# IoT_Greenhouse_V1_0_A_-_Esp32.net
KiCad netlist of a schematic drawn in Altium Designer
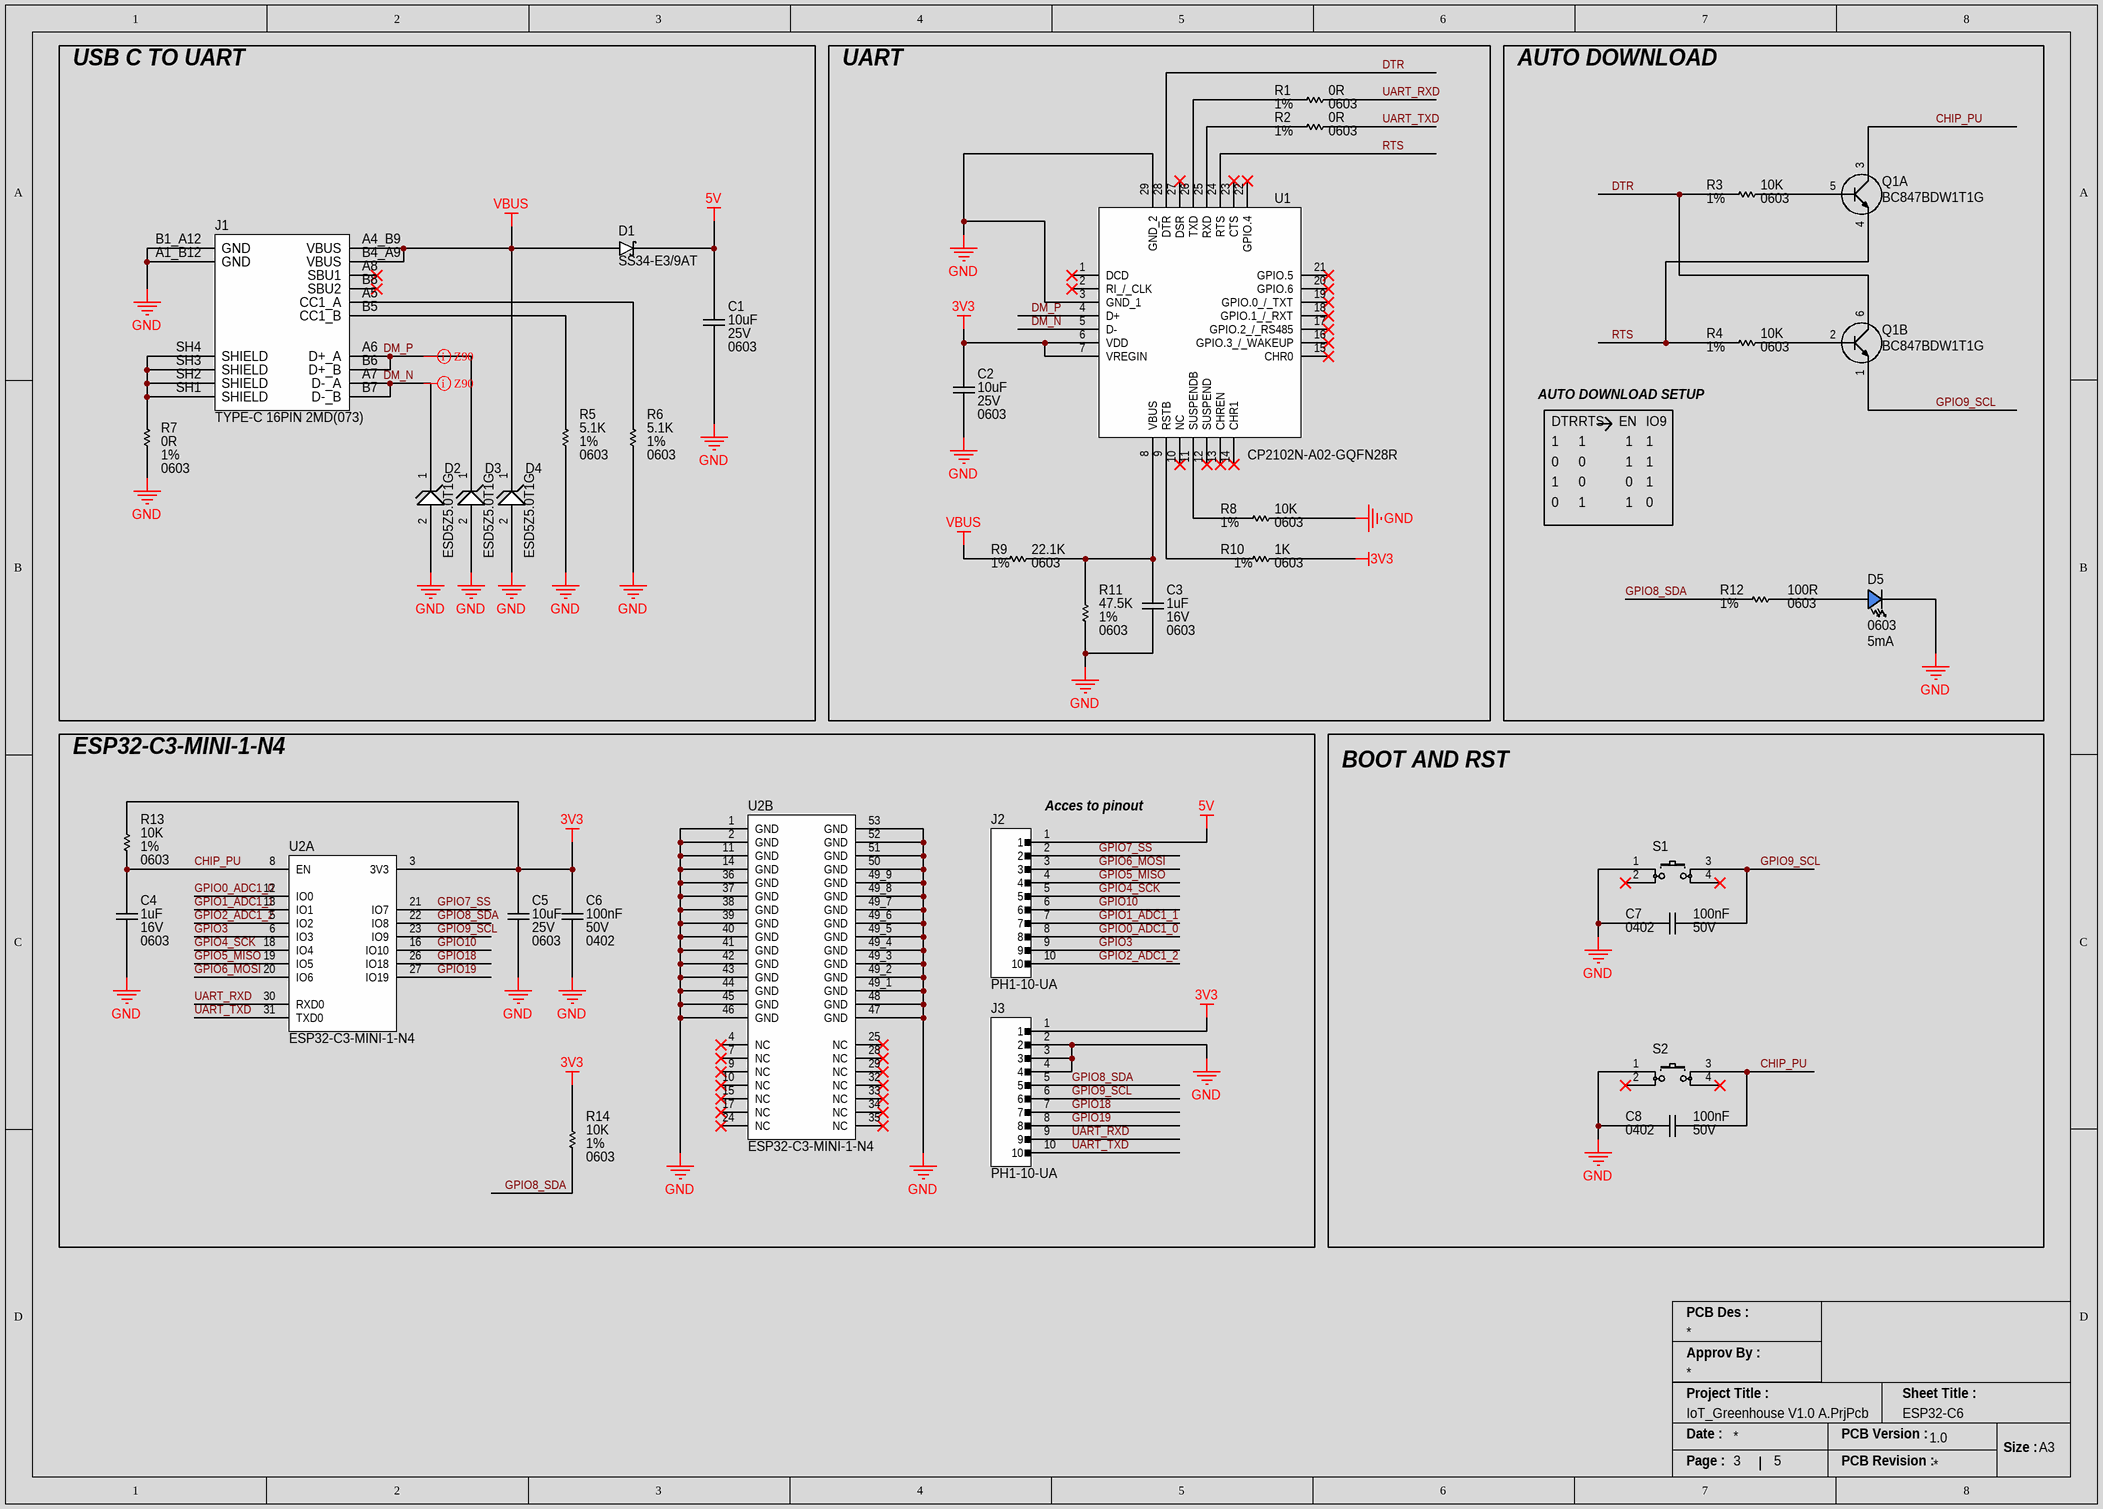
[diagram p0: IoT_Greenhouse V1.0 A - Esp32.SchDoc]

(export (version "E")
  (design (tool "Eeschema 10.0.6"))
  (components
    (comp (ref "C1")
      (value "GRM188R61E106MA73D")
      (footprint "CAP_0603_CAPC1608X08N")
      (description "Multilayer Ceramic Capacitor, 10 uF, 25 V, ± 20%, X5R, 0603 [1608 Metric]")
      (fields
        (field (name "MANUFACTURER") "Murata")
        (field (name "TOLERANCE") "20%")
        (field (name "CASE/PACKAGE") "0603")
        (field (name "CAPACITANCE") "10uF")
        (field (name "VOLTAGE RATING") "25V")
      )
      (libsource (lib "Electronic Devices_LIB") (part "CAP_10UF_25V_X5R_0603"))
    )
    (comp (ref "C2")
      (value "GRM188R61E106MA73D")
      (footprint "CAP_0603_CAPC1608X08N")
      (description "Multilayer Ceramic Capacitor, 10 uF, 25 V, ± 20%, X5R, 0603 [1608 Metric]")
      (fields
        (field (name "MANUFACTURER") "Murata")
        (field (name "TOLERANCE") "20%")
        (field (name "CASE/PACKAGE") "0603")
        (field (name "CAPACITANCE") "10uF")
        (field (name "VOLTAGE RATING") "25V")
      )
      (libsource (lib "Electronic Devices_LIB") (part "CAP_10UF_25V_X5R_0603"))
    )
    (comp (ref "C3")
      (value "CL10A105KO8NNNC")
      (footprint "CAP_0603_CAPC1608X08N")
      (description "CAP CER 1UF 16V X5R 0603")
      (fields
        (field (name "MANUFACTURER") "Samsung")
        (field (name "TOLERANCE") "10%")
        (field (name "VOLTAGE RATING") "16V")
        (field (name "CAPACITANCE") "1uF")
        (field (name "CASE/PACKAGE") "0603")
      )
      (libsource (lib "Electronic Devices_LIB") (part "CAP_1UF_16V_X5R_0603"))
    )
    (comp (ref "C4")
      (value "CL10A105KO8NNNC")
      (footprint "CAP_0603_CAPC1608X08N")
      (description "CAP CER 1UF 16V X5R 0603")
      (fields
        (field (name "MANUFACTURER") "Samsung")
        (field (name "TOLERANCE") "10%")
        (field (name "VOLTAGE RATING") "16V")
        (field (name "CAPACITANCE") "1uF")
        (field (name "CASE/PACKAGE") "0603")
      )
      (libsource (lib "Electronic Devices_LIB") (part "CAP_1UF_16V_X5R_0603"))
    )
    (comp (ref "C5")
      (value "GRM188R61E106MA73D")
      (footprint "CAP_0603_CAPC1608X08N")
      (description "Multilayer Ceramic Capacitor, 10 uF, 25 V, ± 20%, X5R, 0603 [1608 Metric]")
      (fields
        (field (name "MANUFACTURER") "Murata")
        (field (name "TOLERANCE") "20%")
        (field (name "CASE/PACKAGE") "0603")
        (field (name "CAPACITANCE") "10uF")
        (field (name "VOLTAGE RATING") "25V")
      )
      (libsource (lib "Electronic Devices_LIB") (part "CAP_10UF_25V_X5R_0603"))
    )
    (comp (ref "C6")
      (value "GRM155R71H104KE14D")
      (footprint "CAP_0402_CAPC1005X05N")
      (description "Multilayer Ceramic Capacitor, 0.1 uF, 16 V, ± 10%, X7R, 0402 [1005 Metric]")
      (fields
        (field (name "MANUFACTURER") "Murata")
        (field (name "TOLERANCE") "10%")
        (field (name "VOLTAGE RATING") "50V")
        (field (name "CAPACITANCE") "100nF")
        (field (name "CASE/PACKAGE") "0402")
      )
      (libsource (lib "Electronic Devices_LIB") (part "CAP_100NF_50V_X7R_0402"))
    )
    (comp (ref "C7")
      (value "GRM155R71H104KE14D")
      (footprint "CAP_0402_CAPC1005X05N")
      (description "Multilayer Ceramic Capacitor, 0.1 uF, 16 V, ± 10%, X7R, 0402 [1005 Metric]")
      (fields
        (field (name "MANUFACTURER") "Murata")
        (field (name "TOLERANCE") "10%")
        (field (name "VOLTAGE RATING") "50V")
        (field (name "CAPACITANCE") "100nF")
        (field (name "CASE/PACKAGE") "0402")
      )
      (libsource (lib "Electronic Devices_LIB") (part "CAP_100NF_50V_X7R_0402"))
    )
    (comp (ref "C8")
      (value "GRM155R71H104KE14D")
      (footprint "CAP_0402_CAPC1005X05N")
      (description "Multilayer Ceramic Capacitor, 0.1 uF, 16 V, ± 10%, X7R, 0402 [1005 Metric]")
      (fields
        (field (name "MANUFACTURER") "Murata")
        (field (name "TOLERANCE") "10%")
        (field (name "VOLTAGE RATING") "50V")
        (field (name "CAPACITANCE") "100nF")
        (field (name "CASE/PACKAGE") "0402")
      )
      (libsource (lib "Electronic Devices_LIB") (part "CAP_100NF_50V_X7R_0402"))
    )
    (comp (ref "D1")
      (value "SS34-E3/9AT")
      (footprint "DIO_Vishay_SMC_MFG")
      (description "Rectifier Diode, schottky, 40V V(Rrm), do-214Ab / Smc")
      (fields (field (name "MANUFACTURER") "Vishay Semiconductors"))
      (libsource (lib "Electronic Devices_LIB") (part "DIO_SCTKY_40V_3A"))
    )
    (comp (ref "D2")
      (value "ESD5Z5.0T1G")
      (footprint "SOD523_SODFL1608X70N")
      (description "ESD5Z Series 6.2 V 80 pF 5 Vrwm TVS and ESD Protection Diodes - SOD-523")
      (fields (field (name "MANUFACTURER") "ON Semiconductor"))
      (libsource (lib "Electronic Devices_LIB") (part "DIO_TVS_5V_ESD5Z5.0T1G"))
    )
    (comp (ref "D3")
      (value "ESD5Z5.0T1G")
      (footprint "SOD523_SODFL1608X70N")
      (description "ESD5Z Series 6.2 V 80 pF 5 Vrwm TVS and ESD Protection Diodes - SOD-523")
      (fields (field (name "MANUFACTURER") "ON Semiconductor"))
      (libsource (lib "Electronic Devices_LIB") (part "DIO_TVS_5V_ESD5Z5.0T1G"))
    )
    (comp (ref "D4")
      (value "ESD5Z5.0T1G")
      (footprint "SOD523_SODFL1608X70N")
      (description "ESD5Z Series 6.2 V 80 pF 5 Vrwm TVS and ESD Protection Diodes - SOD-523")
      (fields (field (name "MANUFACTURER") "ON Semiconductor"))
      (libsource (lib "Electronic Devices_LIB") (part "DIO_TVS_5V_ESD5Z5.0T1G"))
    )
    (comp (ref "D5")
      (value "LTST-C193TBKT-5A")
      (footprint "LED_0603-BLUE-0.75mm")
      (description "LED Uni-Color Blue 468nm 2-Pin Chip LED T/R")
      (fields
        (field (name "MANUFACTURER") "Vishay Lite-On")
        (field (name "CASE CODE (IMPERIAL)") "0603")
        (field (name "TEST CURRENT") "5mA")
      )
      (libsource (lib "Electronic Devices_LIB") (part "LED_DIO_BLUE_5mA_0603"))
    )
    (comp (ref "J1")
      (value "TYPE-C 16PIN 2MD(073)")
      (footprint "CONN_USB_C_16P")
      (description "5A 1 Surface Mount 16P Female -25℃~+85℃ Type-C SMD USB Connectors ROHS")
      (fields (field (name "MANUFACTURER") "SHOU HAN"))
      (libsource (lib "Electronic Devices_LIB") (part "CONN_USB_TYPEC_2.0_16P_TYPE-C 16PIN 2MD(073)"))
    )
    (comp (ref "J2")
      (value "PH1-10-UA")
      (footprint "CONN_HEADER_MALE_10P")
      (description "Conn Unshrouded Header HDR 12 POS 2.54mm Solder RA Side Entry Thru-Hole Bag")
      (fields (field (name "MANUFACTURER") "Adam Equipment"))
      (libsource (lib "Electronic Devices_LIB") (part "CONN_HEADER_MALE_10P_2.54mm_PH1-10-UA"))
    )
    (comp (ref "J3")
      (value "PH1-10-UA")
      (footprint "CONN_HEADER_MALE_10P")
      (description "Conn Unshrouded Header HDR 12 POS 2.54mm Solder RA Side Entry Thru-Hole Bag")
      (fields (field (name "MANUFACTURER") "Adam Equipment"))
      (libsource (lib "Electronic Devices_LIB") (part "CONN_HEADER_MALE_10P_2.54mm_PH1-10-UA"))
    )
    (comp (ref "Q1")
      (value "BC847BDW1T1G")
      (footprint "TRANS_BJT_SOT65P210X110-6N")
      (description "ON Semi BC847BDW1T1G Dual NPN Bipolar Transistor; 0.1 A; 45 V; 6-Pin SC-88")
      (fields (field (name "MANUFACTURER") "ON Semiconductor"))
      (libsource (lib "Electronic Devices_LIB") (part "TRANS_BIPOLAR_NPN_BC847BDW1T1G"))
    )
    (comp (ref "R1")
      (value "RC0603FR-070RL")
      (footprint "RES_0603_RESC1608X04N")
      (description "RC Series 0603 0.1 W 0 Ohm Jumper Surface Mount Thick Film Chip Resistor")
      (fields
        (field (name "MANUFACTURER") "Yageo")
        (field (name "TOLERANCE") "1%")
        (field (name "RESISTANCE") "0R")
        (field (name "CASE CODE (IMPERIAL)") "0603")
      )
      (libsource (lib "Electronic Devices_LIB") (part "RES_0R_1%_100mW_0603"))
    )
    (comp (ref "R2")
      (value "RC0603FR-070RL")
      (footprint "RES_0603_RESC1608X04N")
      (description "RC Series 0603 0.1 W 0 Ohm Jumper Surface Mount Thick Film Chip Resistor")
      (fields
        (field (name "MANUFACTURER") "Yageo")
        (field (name "TOLERANCE") "1%")
        (field (name "RESISTANCE") "0R")
        (field (name "CASE CODE (IMPERIAL)") "0603")
      )
      (libsource (lib "Electronic Devices_LIB") (part "RES_0R_1%_100mW_0603"))
    )
    (comp (ref "R3")
      (value "AC0603FR-1010KL")
      (footprint "RES_0603_RESC1608X04N")
      (description "Chip Resistor Automotive Grade Thick Film 0603 10kOhm 1% Paper T/R")
      (fields
        (field (name "MANUFACTURER") "Yageo")
        (field (name "RESISTANCE") "10K")
        (field (name "TOLERANCE") "1%")
        (field (name "CASE/PACKAGE") "0603")
      )
      (libsource (lib "Electronic Devices_LIB") (part "RES_10K_1%_100mW_0603"))
    )
    (comp (ref "R4")
      (value "AC0603FR-1010KL")
      (footprint "RES_0603_RESC1608X04N")
      (description "Chip Resistor Automotive Grade Thick Film 0603 10kOhm 1% Paper T/R")
      (fields
        (field (name "MANUFACTURER") "Yageo")
        (field (name "RESISTANCE") "10K")
        (field (name "TOLERANCE") "1%")
        (field (name "CASE/PACKAGE") "0603")
      )
      (libsource (lib "Electronic Devices_LIB") (part "RES_10K_1%_100mW_0603"))
    )
    (comp (ref "R5")
      (value "RC0603FR-075K1L")
      (footprint "RES_0603_RESC1608X04N")
      (description "SMD Chip Resistor, 5.1 kOhm, ± 1%, 100 mW, 0603 [1608 Metric], Thick Film, General Purpose")
      (fields
        (field (name "MANUFACTURER") "Yageo")
        (field (name "TOLERANCE") "1%")
        (field (name "RESISTANCE") "5.1K")
        (field (name "CASE/PACKAGE") "0603")
      )
      (libsource (lib "Electronic Devices_LIB") (part "RES_5.1K_1%_100mW_0603"))
    )
    (comp (ref "R6")
      (value "RC0603FR-075K1L")
      (footprint "RES_0603_RESC1608X04N")
      (description "SMD Chip Resistor, 5.1 kOhm, ± 1%, 100 mW, 0603 [1608 Metric], Thick Film, General Purpose")
      (fields
        (field (name "MANUFACTURER") "Yageo")
        (field (name "TOLERANCE") "1%")
        (field (name "RESISTANCE") "5.1K")
        (field (name "CASE/PACKAGE") "0603")
      )
      (libsource (lib "Electronic Devices_LIB") (part "RES_5.1K_1%_100mW_0603"))
    )
    (comp (ref "R7")
      (value "RC0603FR-070RL")
      (footprint "RES_0603_RESC1608X04N")
      (description "RC Series 0603 0.1 W 0 Ohm Jumper Surface Mount Thick Film Chip Resistor")
      (fields
        (field (name "MANUFACTURER") "Yageo")
        (field (name "TOLERANCE") "1%")
        (field (name "RESISTANCE") "0R")
        (field (name "CASE CODE (IMPERIAL)") "0603")
      )
      (libsource (lib "Electronic Devices_LIB") (part "RES_0R_1%_100mW_0603"))
    )
    (comp (ref "R8")
      (value "AC0603FR-1010KL")
      (footprint "RES_0603_RESC1608X04N")
      (description "Chip Resistor Automotive Grade Thick Film 0603 10kOhm 1% Paper T/R")
      (fields
        (field (name "MANUFACTURER") "Yageo")
        (field (name "RESISTANCE") "10K")
        (field (name "TOLERANCE") "1%")
        (field (name "CASE/PACKAGE") "0603")
      )
      (libsource (lib "Electronic Devices_LIB") (part "RES_10K_1%_100mW_0603"))
    )
    (comp (ref "R9")
      (value "RC0603FR-0722K1L")
      (footprint "RES_0603_RESC1608X04N")
      (description "SMD Chip Resistor, 22.1 kOhm, ± 1%, 100 mW, 0603 [1608 Metric], Thick Film, General Purpose")
      (fields
        (field (name "MANUFACTURER") "Yageo")
        (field (name "RESISTANCE") "22.1K")
        (field (name "TOLERANCE") "1%")
        (field (name "CASE/PACKAGE") "0603")
      )
      (libsource (lib "Electronic Devices_LIB") (part "RES_22.1K_1%_100mW_0603"))
    )
    (comp (ref "R10")
      (value "AC0603FR-101KL")
      (footprint "RES_0603_RESC1608X04N")
      (description "Chip Resistor Automotive Grade Thick Film 0603 1kOhm 1% Paper T/R")
      (fields
        (field (name "MANUFACTURER") "Yageo")
        (field (name "RESISTANCE") "1K")
        (field (name "TOLERANCE") "1%")
        (field (name "CASE/PACKAGE") "0603")
      )
      (libsource (lib "Electronic Devices_LIB") (part "RES_1K_1%_100mW_0603"))
    )
    (comp (ref "R11")
      (value "AC0603FR-0747K5L")
      (footprint "RES_0603_RESC1608X04N")
      (description "SMD Chip Resistor, 47.5 kOhm, ± 1%, 100 mW, 0603 [1608 Metric], Thick Film, General Purpose")
      (fields
        (field (name "MANUFACTURER") "Yageo")
        (field (name "TOLERANCE") "1%")
        (field (name "RESISTANCE") "47.5K")
        (field (name "CASE/PACKAGE") "0603")
      )
      (libsource (lib "Electronic Devices_LIB") (part "RES_47.5K_1%_100mW_0603"))
    )
    (comp (ref "R12")
      (value "ERJ3EKF1000V")
      (footprint "CAP_0603_CAPC1608X08N")
      (description "Res Thick Film 0603 100 Ohm 1% 1/10W ±100ppm/°C Molded SMD Punched Carrier T/R")
      (fields
        (field (name "MANUFACTURER") "Panasonic")
        (field (name "CASE CODE (IMPERIAL)") "0603")
        (field (name "TOLERANCE") "1%")
        (field (name "RESISTANCE") "100R")
      )
      (libsource (lib "Electronic Devices_LIB") (part "RES_100R_1%_100MW_0603"))
    )
    (comp (ref "R13")
      (value "AC0603FR-1010KL")
      (footprint "RES_0603_RESC1608X04N")
      (description "Chip Resistor Automotive Grade Thick Film 0603 10kOhm 1% Paper T/R")
      (fields
        (field (name "MANUFACTURER") "Yageo")
        (field (name "RESISTANCE") "10K")
        (field (name "TOLERANCE") "1%")
        (field (name "CASE/PACKAGE") "0603")
      )
      (libsource (lib "Electronic Devices_LIB") (part "RES_10K_1%_100mW_0603"))
    )
    (comp (ref "R14")
      (value "AC0603FR-1010KL")
      (footprint "RES_0603_RESC1608X04N")
      (description "Chip Resistor Automotive Grade Thick Film 0603 10kOhm 1% Paper T/R")
      (fields
        (field (name "MANUFACTURER") "Yageo")
        (field (name "RESISTANCE") "10K")
        (field (name "TOLERANCE") "1%")
        (field (name "CASE/PACKAGE") "0603")
      )
      (libsource (lib "Electronic Devices_LIB") (part "RES_10K_1%_100mW_0603"))
    )
    (comp (ref "S1")
      (value "PTS526SK15SMTR2LFS")
      (footprint "SWT_NO_PTS526SK15SMTR2LFS")
      (description "Switch Tactile N.O. SPST Round Button Gull Wing 0.05A 12VDC 200000Cycles 2.55N SMD T/R")
      (fields (field (name "MANUFACTURER") "ITT C&K"))
      (libsource (lib "Electronic Devices_LIB") (part "SWITCH_NO_SPST_0.05A"))
    )
    (comp (ref "S2")
      (value "PTS526SK15SMTR2LFS")
      (footprint "SWT_NO_PTS526SK15SMTR2LFS")
      (description "Switch Tactile N.O. SPST Round Button Gull Wing 0.05A 12VDC 200000Cycles 2.55N SMD T/R")
      (fields (field (name "MANUFACTURER") "ITT C&K"))
      (libsource (lib "Electronic Devices_LIB") (part "SWITCH_NO_SPST_0.05A"))
    )
    (comp (ref "U1")
      (value "CP2102N-A02-GQFN28R")
      (footprint "IC_BRIDGE_UART_QFN50P500X500X80-29N-D")
      (description "Full Speed USB to UART Bridge USB 2.0 3.3V T/R Automotive 28-Pin QFN EP")
      (fields (field (name "MANUFACTURER") "Silicon Labs"))
      (libsource (lib "Electronic Devices_LIB") (part "IC_BRIDGE_UART_CP2102N-A02-GQFN28R"))
    )
    (comp (ref "U2")
      (value "ESP32-C3-MINI-1-N4")
      (footprint "XCVR_ESP32-C3-MINI-1-N4")
      (description "Multiprotocol Modules SMD module, ESP32-C3FN4, PCB antenna, -40 C +85 C")
      (fields (field (name "MANUFACTURER") "Espressif Systems"))
      (libsource (lib "Electronic Devices_LIB") (part "IC_MODULE_ESP32-C3-MINI-1-N4"))
    )
  )
  (nets
    (net (code "1") (name "/CHIP_PU") (class "Default")
      (node (ref "C4") (pin "2") (pinfunction "2_2") (pintype "passive"))
      (node (ref "C8") (pin "1") (pinfunction "1_1") (pintype "passive"))
      (node (ref "Q1") (pin "3") (pinfunction "COLLECTOR_1_3") (pintype "passive"))
      (node (ref "R13") (pin "2") (pinfunction "2_2") (pintype "passive"))
      (node (ref "S2") (pin "3") (pinfunction "NO1_3") (pintype "passive"))
      (node (ref "U2") (pin "8") (pinfunction "EN_8") (pintype "passive"))
    )
    (net (code "2") (name "/DM_N") (class "Default")
      (node (ref "D2") (pin "1") (pinfunction "K_1") (pintype "passive"))
      (node (ref "J1") (pin "A7") (pinfunction "D-_A_A7") (pintype "passive"))
      (node (ref "J1") (pin "B7") (pinfunction "D-_B_B7") (pintype "passive"))
      (node (ref "U1") (pin "5") (pinfunction "D-_5") (pintype "passive"))
    )
    (net (code "3") (name "/DM_P") (class "Default")
      (node (ref "D3") (pin "1") (pinfunction "K_1") (pintype "passive"))
      (node (ref "J1") (pin "A6") (pinfunction "D+_A_A6") (pintype "passive"))
      (node (ref "J1") (pin "B6") (pinfunction "D+_B_B6") (pintype "passive"))
      (node (ref "U1") (pin "4") (pinfunction "D+_4") (pintype "passive"))
    )
    (net (code "4") (name "/DTR") (class "Default")
      (node (ref "Q1") (pin "6") (pinfunction "COLLECTOR_2_6") (pintype "passive"))
      (node (ref "R3") (pin "2") (pinfunction "2_2") (pintype "passive"))
      (node (ref "U1") (pin "28") (pinfunction "DTR_28") (pintype "passive"))
    )
    (net (code "5") (name "/GPIO0_ADC1_0") (class "Default")
      (node (ref "J2") (pin "8") (pinfunction "8_8") (pintype "passive"))
      (node (ref "U2") (pin "12") (pinfunction "IO0_12") (pintype "passive"))
    )
    (net (code "6") (name "/GPIO1_ADC1_1") (class "Default")
      (node (ref "J2") (pin "7") (pinfunction "7_7") (pintype "passive"))
      (node (ref "U2") (pin "13") (pinfunction "IO1_13") (pintype "passive"))
    )
    (net (code "7") (name "/GPIO2_ADC1_2") (class "Default")
      (node (ref "J2") (pin "10") (pinfunction "10_10") (pintype "passive"))
      (node (ref "U2") (pin "5") (pinfunction "IO2_5") (pintype "passive"))
    )
    (net (code "8") (name "/GPIO3") (class "Default")
      (node (ref "J2") (pin "9") (pinfunction "9_9") (pintype "passive"))
      (node (ref "U2") (pin "6") (pinfunction "IO3_6") (pintype "passive"))
    )
    (net (code "9") (name "/GPIO4_SCK") (class "Default")
      (node (ref "J2") (pin "5") (pinfunction "5_5") (pintype "passive"))
      (node (ref "U2") (pin "18") (pinfunction "IO4_18") (pintype "passive"))
    )
    (net (code "10") (name "/GPIO5_MISO") (class "Default")
      (node (ref "J2") (pin "4") (pinfunction "4_4") (pintype "passive"))
      (node (ref "U2") (pin "19") (pinfunction "IO5_19") (pintype "passive"))
    )
    (net (code "11") (name "/GPIO6_MOSI") (class "Default")
      (node (ref "J2") (pin "3") (pinfunction "3_3") (pintype "passive"))
      (node (ref "U2") (pin "20") (pinfunction "IO6_20") (pintype "passive"))
    )
    (net (code "12") (name "/GPIO7_SS") (class "Default")
      (node (ref "J2") (pin "2") (pinfunction "2_2") (pintype "passive"))
      (node (ref "U2") (pin "21") (pinfunction "IO7_21") (pintype "passive"))
    )
    (net (code "13") (name "/GPIO8_SDA") (class "Default")
      (node (ref "J3") (pin "5") (pinfunction "5_5") (pintype "passive"))
      (node (ref "R12") (pin "1") (pinfunction "1_1") (pintype "passive"))
      (node (ref "R14") (pin "2") (pinfunction "2_2") (pintype "passive"))
      (node (ref "U2") (pin "22") (pinfunction "IO8_22") (pintype "passive"))
    )
    (net (code "14") (name "/GPIO9_SCL") (class "Default")
      (node (ref "C7") (pin "1") (pinfunction "1_1") (pintype "passive"))
      (node (ref "J3") (pin "6") (pinfunction "6_6") (pintype "passive"))
      (node (ref "Q1") (pin "1") (pinfunction "EMITTER_2_1") (pintype "passive"))
      (node (ref "S1") (pin "3") (pinfunction "NO1_3") (pintype "passive"))
      (node (ref "U2") (pin "23") (pinfunction "IO9_23") (pintype "passive"))
    )
    (net (code "15") (name "/GPIO10") (class "Default")
      (node (ref "J2") (pin "6") (pinfunction "6_6") (pintype "passive"))
      (node (ref "U2") (pin "16") (pinfunction "IO10_16") (pintype "passive"))
    )
    (net (code "16") (name "/GPIO18") (class "Default")
      (node (ref "J3") (pin "7") (pinfunction "7_7") (pintype "passive"))
      (node (ref "U2") (pin "26") (pinfunction "IO18_26") (pintype "passive"))
    )
    (net (code "17") (name "/GPIO19") (class "Default")
      (node (ref "J3") (pin "8") (pinfunction "8_8") (pintype "passive"))
      (node (ref "U2") (pin "27") (pinfunction "IO19_27") (pintype "passive"))
    )
    (net (code "18") (name "/RTS") (class "Default")
      (node (ref "Q1") (pin "4") (pinfunction "EMITTER_1_4") (pintype "passive"))
      (node (ref "R4") (pin "2") (pinfunction "2_2") (pintype "passive"))
      (node (ref "U1") (pin "24") (pinfunction "RTS_24") (pintype "passive"))
    )
    (net (code "19") (name "/UART_RXD") (class "Default")
      (node (ref "J3") (pin "9") (pinfunction "9_9") (pintype "passive"))
      (node (ref "R1") (pin "1") (pinfunction "1_1") (pintype "passive"))
      (node (ref "U2") (pin "30") (pinfunction "RXD0_30") (pintype "passive"))
    )
    (net (code "20") (name "/UART_TXD") (class "Default")
      (node (ref "J3") (pin "10") (pinfunction "10_10") (pintype "passive"))
      (node (ref "R2") (pin "1") (pinfunction "1_1") (pintype "passive"))
      (node (ref "U2") (pin "31") (pinfunction "TXD0_31") (pintype "passive"))
    )
    (net (code "21") (name "3V3") (class "Default")
      (node (ref "C2") (pin "2") (pinfunction "2_2") (pintype "passive"))
      (node (ref "C5") (pin "2") (pinfunction "2_2") (pintype "passive"))
      (node (ref "C6") (pin "2") (pinfunction "2_2") (pintype "passive"))
      (node (ref "J3") (pin "1") (pinfunction "1_1") (pintype "passive"))
      (node (ref "R10") (pin "2") (pinfunction "2_2") (pintype "passive"))
      (node (ref "R13") (pin "1") (pinfunction "1_1") (pintype "passive"))
      (node (ref "R14") (pin "1") (pinfunction "1_1") (pintype "passive"))
      (node (ref "U1") (pin "6") (pinfunction "VDD_6") (pintype "passive"))
      (node (ref "U1") (pin "7") (pinfunction "VREGIN_7") (pintype "passive"))
      (node (ref "U2") (pin "3") (pinfunction "3V3_3") (pintype "passive"))
    )
    (net (code "22") (name "5V") (class "Default")
      (node (ref "C1") (pin "2") (pinfunction "2_2") (pintype "passive"))
      (node (ref "D1") (pin "1") (pinfunction "K_1") (pintype "passive"))
      (node (ref "J2") (pin "1") (pinfunction "1_1") (pintype "passive"))
    )
    (net (code "23") (name "GND") (class "Default")
      (node (ref "C1") (pin "1") (pinfunction "1_1") (pintype "passive"))
      (node (ref "C2") (pin "1") (pinfunction "1_1") (pintype "passive"))
      (node (ref "C3") (pin "1") (pinfunction "1_1") (pintype "passive"))
      (node (ref "C4") (pin "1") (pinfunction "1_1") (pintype "passive"))
      (node (ref "C5") (pin "1") (pinfunction "1_1") (pintype "passive"))
      (node (ref "C6") (pin "1") (pinfunction "1_1") (pintype "passive"))
      (node (ref "C7") (pin "2") (pinfunction "2_2") (pintype "passive"))
      (node (ref "C8") (pin "2") (pinfunction "2_2") (pintype "passive"))
      (node (ref "D2") (pin "2") (pinfunction "A_2") (pintype "passive"))
      (node (ref "D3") (pin "2") (pinfunction "A_2") (pintype "passive"))
      (node (ref "D4") (pin "2") (pinfunction "A_2") (pintype "passive"))
      (node (ref "D5") (pin "1") (pinfunction "C_1") (pintype "passive"))
      (node (ref "J1") (pin "A1_B12") (pinfunction "GND_A1_B12") (pintype "power_in"))
      (node (ref "J1") (pin "B1_A12") (pinfunction "GND_B1_A12") (pintype "power_in"))
      (node (ref "J3") (pin "2") (pinfunction "2_2") (pintype "passive"))
      (node (ref "J3") (pin "3") (pinfunction "3_3") (pintype "passive"))
      (node (ref "J3") (pin "4") (pinfunction "4_4") (pintype "passive"))
      (node (ref "R11") (pin "1") (pinfunction "1_1") (pintype "passive"))
      (node (ref "R5") (pin "1") (pinfunction "1_1") (pintype "passive"))
      (node (ref "R6") (pin "1") (pinfunction "1_1") (pintype "passive"))
      (node (ref "R7") (pin "1") (pinfunction "1_1") (pintype "passive"))
      (node (ref "R8") (pin "2") (pinfunction "2_2") (pintype "passive"))
      (node (ref "S1") (pin "1") (pinfunction "COM_1_1") (pintype "passive"))
      (node (ref "S2") (pin "1") (pinfunction "COM_1_1") (pintype "passive"))
      (node (ref "U1") (pin "29") (pinfunction "GND_2_29") (pintype "passive"))
      (node (ref "U1") (pin "3") (pinfunction "GND_1_3") (pintype "passive"))
      (node (ref "U2") (pin "1") (pinfunction "GND_1") (pintype "power_in"))
      (node (ref "U2") (pin "11") (pinfunction "GND_11") (pintype "power_in"))
      (node (ref "U2") (pin "14") (pinfunction "GND_14") (pintype "power_in"))
      (node (ref "U2") (pin "2") (pinfunction "GND_2") (pintype "power_in"))
      (node (ref "U2") (pin "36") (pinfunction "GND_36") (pintype "power_in"))
      (node (ref "U2") (pin "37") (pinfunction "GND_37") (pintype "power_in"))
      (node (ref "U2") (pin "38") (pinfunction "GND_38") (pintype "power_in"))
      (node (ref "U2") (pin "39") (pinfunction "GND_39") (pintype "power_in"))
      (node (ref "U2") (pin "40") (pinfunction "GND_40") (pintype "power_in"))
      (node (ref "U2") (pin "41") (pinfunction "GND_41") (pintype "power_in"))
      (node (ref "U2") (pin "42") (pinfunction "GND_42") (pintype "power_in"))
      (node (ref "U2") (pin "43") (pinfunction "GND_43") (pintype "power_in"))
      (node (ref "U2") (pin "44") (pinfunction "GND_44") (pintype "power_in"))
      (node (ref "U2") (pin "45") (pinfunction "GND_45") (pintype "power_in"))
      (node (ref "U2") (pin "46") (pinfunction "GND_46") (pintype "power_in"))
      (node (ref "U2") (pin "47") (pinfunction "GND_47") (pintype "power_in"))
      (node (ref "U2") (pin "48") (pinfunction "GND_48") (pintype "power_in"))
      (node (ref "U2") (pin "49_1") (pinfunction "GND_49_1") (pintype "power_in"))
      (node (ref "U2") (pin "49_2") (pinfunction "GND_49_2") (pintype "power_in"))
      (node (ref "U2") (pin "49_3") (pinfunction "GND_49_3") (pintype "power_in"))
      (node (ref "U2") (pin "49_4") (pinfunction "GND_49_4") (pintype "power_in"))
      (node (ref "U2") (pin "49_5") (pinfunction "GND_49_5") (pintype "power_in"))
      (node (ref "U2") (pin "49_6") (pinfunction "GND_49_6") (pintype "power_in"))
      (node (ref "U2") (pin "49_7") (pinfunction "GND_49_7") (pintype "power_in"))
      (node (ref "U2") (pin "49_8") (pinfunction "GND_49_8") (pintype "power_in"))
      (node (ref "U2") (pin "49_9") (pinfunction "GND_49_9") (pintype "power_in"))
      (node (ref "U2") (pin "50") (pinfunction "GND_50") (pintype "power_in"))
      (node (ref "U2") (pin "51") (pinfunction "GND_51") (pintype "power_in"))
      (node (ref "U2") (pin "52") (pinfunction "GND_52") (pintype "power_in"))
      (node (ref "U2") (pin "53") (pinfunction "GND_53") (pintype "power_in"))
    )
    (net (code "24") (name "Net-(D5-A)") (class "Default")
      (node (ref "D5") (pin "2") (pinfunction "A_2") (pintype "passive"))
      (node (ref "R12") (pin "2") (pinfunction "2_2") (pintype "passive"))
    )
    (net (code "25") (name "Net-(J1-CC1_A)") (class "Default")
      (node (ref "J1") (pin "A5") (pinfunction "CC1_A_A5") (pintype "passive"))
      (node (ref "R6") (pin "2") (pinfunction "2_2") (pintype "passive"))
    )
    (net (code "26") (name "Net-(J1-CC1_B)") (class "Default")
      (node (ref "J1") (pin "B5") (pinfunction "CC1_B_B5") (pintype "passive"))
      (node (ref "R5") (pin "2") (pinfunction "2_2") (pintype "passive"))
    )
    (net (code "27") (name "Net-(J1-SHIELD-PadSH1)") (class "Default")
      (node (ref "J1") (pin "SH1") (pinfunction "SHIELD_SH1") (pintype "passive"))
      (node (ref "J1") (pin "SH2") (pinfunction "SHIELD_SH2") (pintype "passive"))
      (node (ref "J1") (pin "SH3") (pinfunction "SHIELD_SH3") (pintype "passive"))
      (node (ref "J1") (pin "SH4") (pinfunction "SHIELD_SH4") (pintype "passive"))
      (node (ref "R7") (pin "2") (pinfunction "2_2") (pintype "passive"))
    )
    (net (code "28") (name "Net-(Q1A-BASE_1)") (class "Default")
      (node (ref "Q1") (pin "5") (pinfunction "BASE_1_5") (pintype "passive"))
      (node (ref "R3") (pin "1") (pinfunction "1_1") (pintype "passive"))
    )
    (net (code "29") (name "Net-(Q1B-BASE_2)") (class "Default")
      (node (ref "Q1") (pin "2") (pinfunction "BASE_2_2") (pintype "passive"))
      (node (ref "R4") (pin "1") (pinfunction "1_1") (pintype "passive"))
    )
    (net (code "30") (name "Net-(U1-RSTB)") (class "Default")
      (node (ref "R10") (pin "1") (pinfunction "1_1") (pintype "passive"))
      (node (ref "U1") (pin "9") (pinfunction "RSTB_9") (pintype "passive"))
    )
    (net (code "31") (name "Net-(U1-RXD)") (class "Default")
      (node (ref "R2") (pin "2") (pinfunction "2_2") (pintype "passive"))
      (node (ref "U1") (pin "25") (pinfunction "RXD_25") (pintype "passive"))
    )
    (net (code "32") (name "Net-(U1-SUSPENDB)") (class "Default")
      (node (ref "R8") (pin "1") (pinfunction "1_1") (pintype "passive"))
      (node (ref "U1") (pin "11") (pinfunction "SUSPENDB_11") (pintype "passive"))
    )
    (net (code "33") (name "Net-(U1-TXD)") (class "Default")
      (node (ref "R1") (pin "2") (pinfunction "2_2") (pintype "passive"))
      (node (ref "U1") (pin "26") (pinfunction "TXD_26") (pintype "passive"))
    )
    (net (code "34") (name "Net-(U1-VBUS)") (class "Default")
      (node (ref "C3") (pin "2") (pinfunction "2_2") (pintype "passive"))
      (node (ref "R11") (pin "2") (pinfunction "2_2") (pintype "passive"))
      (node (ref "R9") (pin "2") (pinfunction "2_2") (pintype "passive"))
      (node (ref "U1") (pin "8") (pinfunction "VBUS_8") (pintype "passive"))
    )
    (net (code "35") (name "VBUS") (class "Default")
      (node (ref "D1") (pin "2") (pinfunction "A_2") (pintype "passive"))
      (node (ref "D4") (pin "1") (pinfunction "K_1") (pintype "passive"))
      (node (ref "J1") (pin "A4_B9") (pinfunction "VBUS_A4_B9") (pintype "power_in"))
      (node (ref "J1") (pin "B4_A9") (pinfunction "VBUS_B4_A9") (pintype "power_in"))
      (node (ref "R9") (pin "1") (pinfunction "1_1") (pintype "passive"))
    )
    (net (code "36") (name "unconnected-(J1-SBU1-PadA8)") (class "Default")
      (node (ref "J1") (pin "A8") (pinfunction "SBU1_A8") (pintype "passive+no_connect"))
    )
    (net (code "37") (name "unconnected-(J1-SBU2-PadB8)") (class "Default")
      (node (ref "J1") (pin "B8") (pinfunction "SBU2_B8") (pintype "passive+no_connect"))
    )
    (net (code "38") (name "unconnected-(S1-COM2-Pad2)") (class "Default")
      (node (ref "S1") (pin "2") (pinfunction "COM2_2") (pintype "passive+no_connect"))
    )
    (net (code "39") (name "unconnected-(S1-NO2-Pad4)") (class "Default")
      (node (ref "S1") (pin "4") (pinfunction "NO2_4") (pintype "passive+no_connect"))
    )
    (net (code "40") (name "unconnected-(S2-COM2-Pad2)") (class "Default")
      (node (ref "S2") (pin "2") (pinfunction "COM2_2") (pintype "passive+no_connect"))
    )
    (net (code "41") (name "unconnected-(S2-NO2-Pad4)") (class "Default")
      (node (ref "S2") (pin "4") (pinfunction "NO2_4") (pintype "passive+no_connect"))
    )
    (net (code "42") (name "unconnected-(U1-CHR0-Pad15)") (class "Default")
      (node (ref "U1") (pin "15") (pinfunction "CHR0_15") (pintype "passive+no_connect"))
    )
    (net (code "43") (name "unconnected-(U1-CHR1-Pad14)") (class "Default")
      (node (ref "U1") (pin "14") (pinfunction "CHR1_14") (pintype "passive+no_connect"))
    )
    (net (code "44") (name "unconnected-(U1-CHREN-Pad13)") (class "Default")
      (node (ref "U1") (pin "13") (pinfunction "CHREN_13") (pintype "passive+no_connect"))
    )
    (net (code "45") (name "unconnected-(U1-CTS-Pad23)") (class "Default")
      (node (ref "U1") (pin "23") (pinfunction "CTS_23") (pintype "passive+no_connect"))
    )
    (net (code "46") (name "unconnected-(U1-DCD-Pad1)") (class "Default")
      (node (ref "U1") (pin "1") (pinfunction "DCD_1") (pintype "passive+no_connect"))
    )
    (net (code "47") (name "unconnected-(U1-DSR-Pad27)") (class "Default")
      (node (ref "U1") (pin "27") (pinfunction "DSR_27") (pintype "passive+no_connect"))
    )
    (net (code "48") (name "unconnected-(U1-GPIO.0_{slash}_TXT-Pad19)") (class "Default")
      (node (ref "U1") (pin "19") (pinfunction "GPIO.0_/_TXT_19") (pintype "passive+no_connect"))
    )
    (net (code "49") (name "unconnected-(U1-GPIO.1_{slash}_RXT-Pad18)") (class "Default")
      (node (ref "U1") (pin "18") (pinfunction "GPIO.1_/_RXT_18") (pintype "passive+no_connect"))
    )
    (net (code "50") (name "unconnected-(U1-GPIO.2_{slash}_RS485-Pad17)") (class "Default")
      (node (ref "U1") (pin "17") (pinfunction "GPIO.2_/_RS485_17") (pintype "passive+no_connect"))
    )
    (net (code "51") (name "unconnected-(U1-GPIO.3_{slash}_WAKEUP-Pad16)") (class "Default")
      (node (ref "U1") (pin "16") (pinfunction "GPIO.3_/_WAKEUP_16") (pintype "passive+no_connect"))
    )
    (net (code "52") (name "unconnected-(U1-GPIO.4-Pad22)") (class "Default")
      (node (ref "U1") (pin "22") (pinfunction "GPIO.4_22") (pintype "passive+no_connect"))
    )
    (net (code "53") (name "unconnected-(U1-GPIO.5-Pad21)") (class "Default")
      (node (ref "U1") (pin "21") (pinfunction "GPIO.5_21") (pintype "passive+no_connect"))
    )
    (net (code "54") (name "unconnected-(U1-GPIO.6-Pad20)") (class "Default")
      (node (ref "U1") (pin "20") (pinfunction "GPIO.6_20") (pintype "passive+no_connect"))
    )
    (net (code "55") (name "unconnected-(U1-NC-Pad10)") (class "Default")
      (node (ref "U1") (pin "10") (pinfunction "NC_10") (pintype "passive+no_connect"))
    )
    (net (code "56") (name "unconnected-(U1-RI_{slash}_CLK-Pad2)") (class "Default")
      (node (ref "U1") (pin "2") (pinfunction "RI_/_CLK_2") (pintype "passive+no_connect"))
    )
    (net (code "57") (name "unconnected-(U1-SUSPEND-Pad12)") (class "Default")
      (node (ref "U1") (pin "12") (pinfunction "SUSPEND_12") (pintype "passive+no_connect"))
    )
    (net (code "58") (name "unconnected-(U2B-NC-Pad4)") (class "Default")
      (node (ref "U2") (pin "4") (pinfunction "NC_4") (pintype "passive+no_connect"))
    )
    (net (code "59") (name "unconnected-(U2B-NC-Pad7)") (class "Default")
      (node (ref "U2") (pin "7") (pinfunction "NC_7") (pintype "passive+no_connect"))
    )
    (net (code "60") (name "unconnected-(U2B-NC-Pad9)") (class "Default")
      (node (ref "U2") (pin "9") (pinfunction "NC_9") (pintype "passive+no_connect"))
    )
    (net (code "61") (name "unconnected-(U2B-NC-Pad10)") (class "Default")
      (node (ref "U2") (pin "10") (pinfunction "NC_10") (pintype "passive+no_connect"))
    )
    (net (code "62") (name "unconnected-(U2B-NC-Pad15)") (class "Default")
      (node (ref "U2") (pin "15") (pinfunction "NC_15") (pintype "passive+no_connect"))
    )
    (net (code "63") (name "unconnected-(U2B-NC-Pad17)") (class "Default")
      (node (ref "U2") (pin "17") (pinfunction "NC_17") (pintype "passive+no_connect"))
    )
    (net (code "64") (name "unconnected-(U2B-NC-Pad24)") (class "Default")
      (node (ref "U2") (pin "24") (pinfunction "NC_24") (pintype "passive+no_connect"))
    )
    (net (code "65") (name "unconnected-(U2B-NC-Pad25)") (class "Default")
      (node (ref "U2") (pin "25") (pinfunction "NC_25") (pintype "passive+no_connect"))
    )
    (net (code "66") (name "unconnected-(U2B-NC-Pad28)") (class "Default")
      (node (ref "U2") (pin "28") (pinfunction "NC_28") (pintype "passive+no_connect"))
    )
    (net (code "67") (name "unconnected-(U2B-NC-Pad29)") (class "Default")
      (node (ref "U2") (pin "29") (pinfunction "NC_29") (pintype "passive+no_connect"))
    )
    (net (code "68") (name "unconnected-(U2B-NC-Pad32)") (class "Default")
      (node (ref "U2") (pin "32") (pinfunction "NC_32") (pintype "passive+no_connect"))
    )
    (net (code "69") (name "unconnected-(U2B-NC-Pad33)") (class "Default")
      (node (ref "U2") (pin "33") (pinfunction "NC_33") (pintype "passive+no_connect"))
    )
    (net (code "70") (name "unconnected-(U2B-NC-Pad34)") (class "Default")
      (node (ref "U2") (pin "34") (pinfunction "NC_34") (pintype "passive+no_connect"))
    )
    (net (code "71") (name "unconnected-(U2B-NC-Pad35)") (class "Default")
      (node (ref "U2") (pin "35") (pinfunction "NC_35") (pintype "passive+no_connect"))
    )
  )
)
